# ProjSchematic.net
KiCad netlist of a schematic drawn in EAGLE
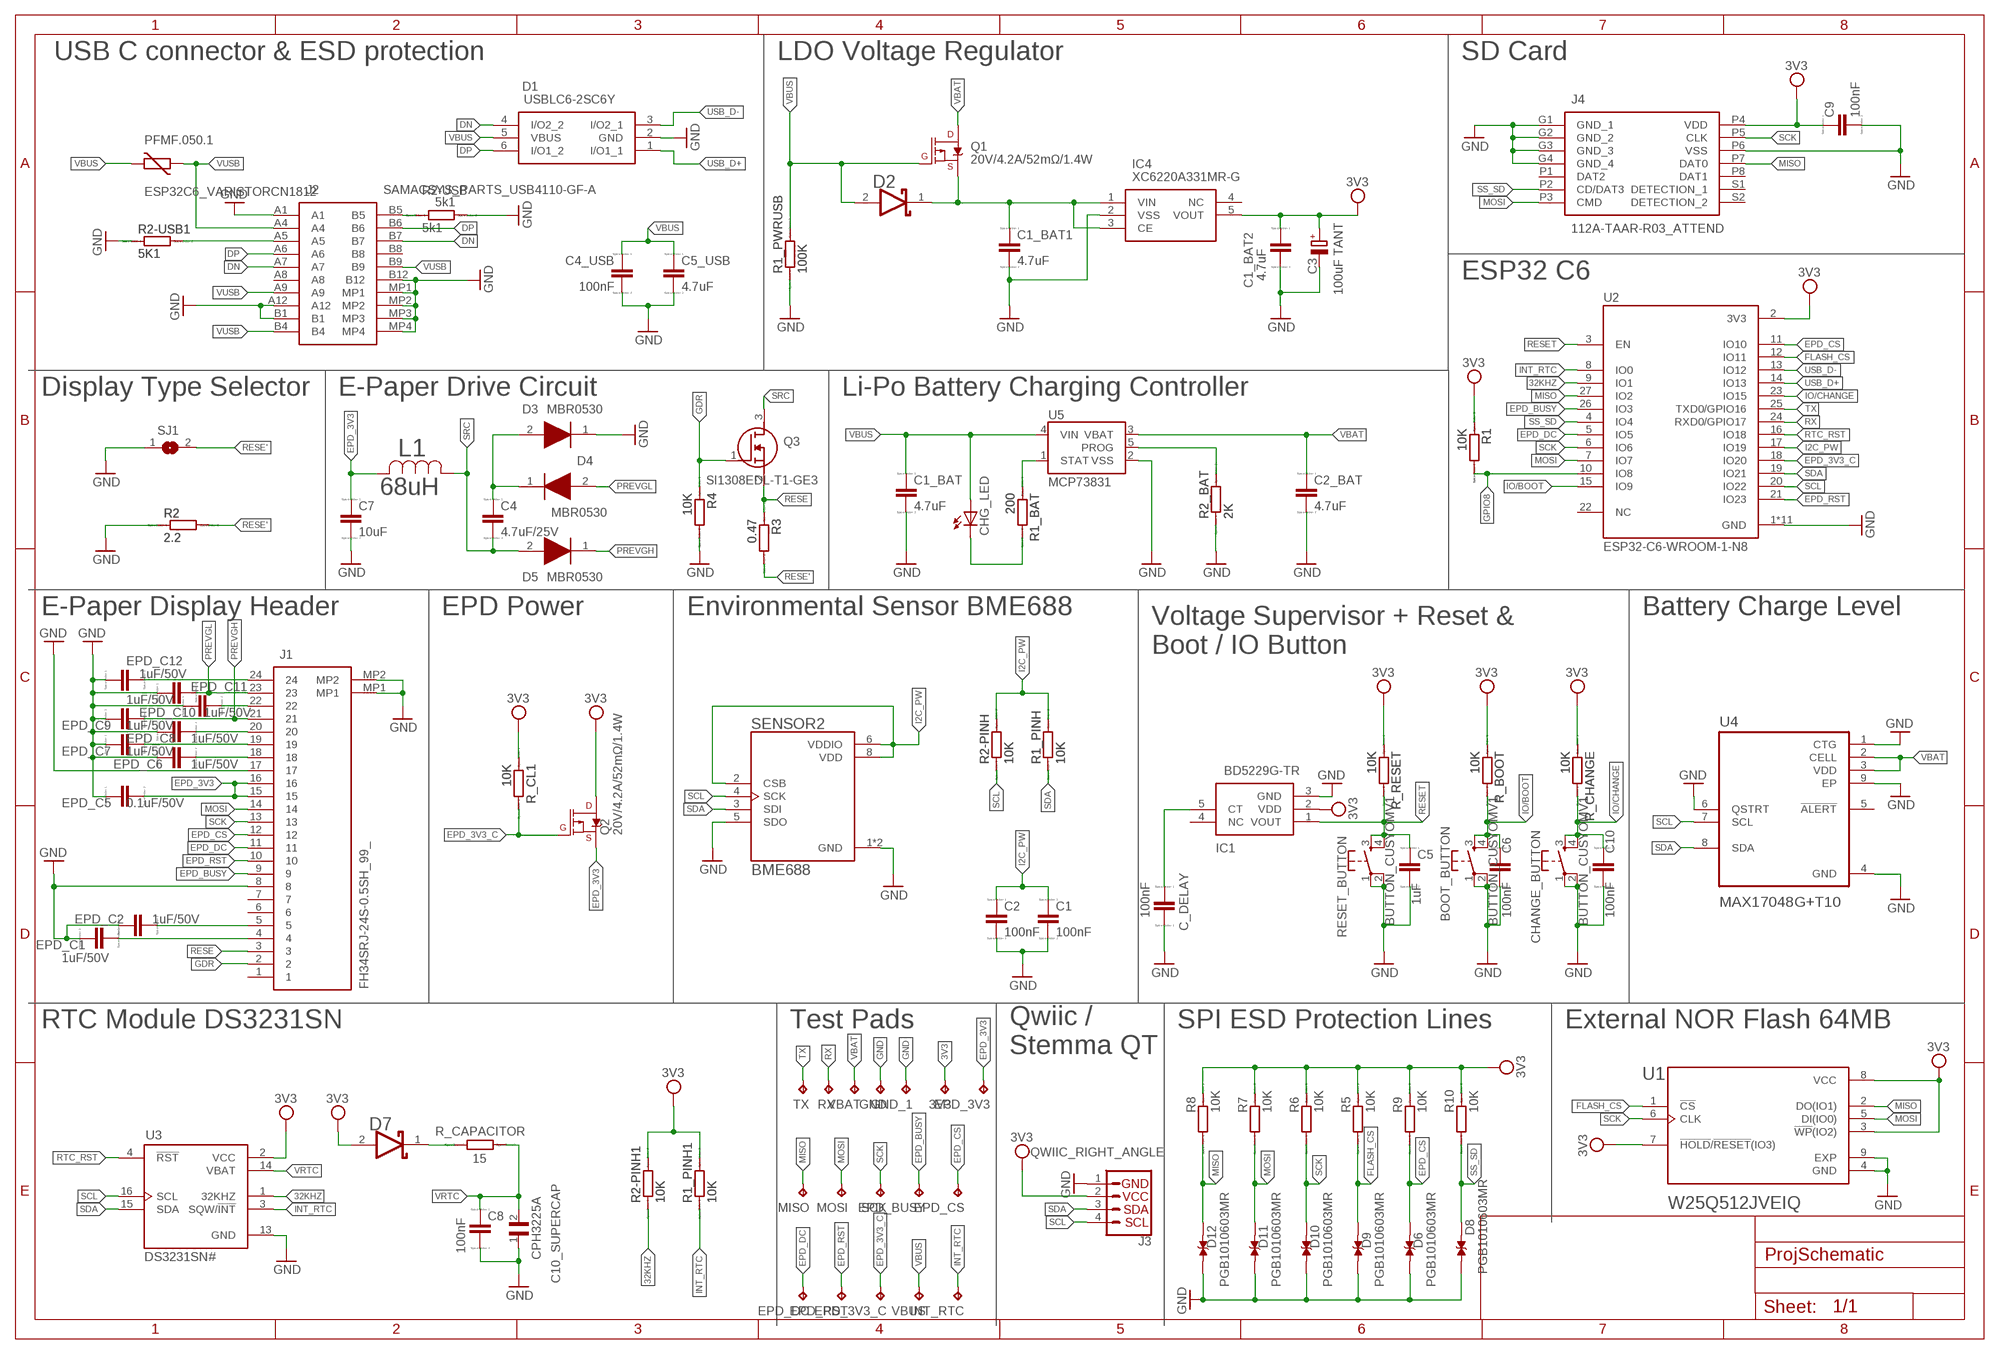
[diagram p0: schematic, sheet 1]

(export (version "E")
  (design (tool "Eeschema 10.0.6"))
  (components
    (comp (ref "3V3")
      (value "TPTP20R")
      (footprint "eagle-import:TP20R")
      (libsource (lib "eagle-import") (part "TPTP20R"))
    )
    (comp (ref "BOOT_BUTTON")
      (value "BUTTON_CUSYOMV1")
      (footprint "eagle-import:MYBUTTON")
      (libsource (lib "eagle-import") (part "BUTTON_CUSYOMV1"))
    )
    (comp (ref "C1")
      (value "100nF")
      (footprint "eagle-import:ESP32_WROVER_EAGLE-LTSPICE_C0402")
      (libsource (lib "eagle-import") (part "ESP32_WROVER_EAGLE-LTSPICE_CC0402"))
    )
    (comp (ref "C1_BAT")
      (value "4.7uF")
      (footprint "eagle-import:ESP32_WROVER_EAGLE-LTSPICE_C0402")
      (libsource (lib "eagle-import") (part "ESP32_WROVER_EAGLE-LTSPICE_CC0402"))
    )
    (comp (ref "C1_BAT1")
      (value "4.7uF")
      (footprint "eagle-import:ESP32_WROVER_EAGLE-LTSPICE_C0402")
      (libsource (lib "eagle-import") (part "ESP32_WROVER_EAGLE-LTSPICE_CC0402"))
    )
    (comp (ref "C1_BAT2")
      (value "4.7uF")
      (footprint "eagle-import:ESP32_WROVER_EAGLE-LTSPICE_C0402")
      (libsource (lib "eagle-import") (part "ESP32_WROVER_EAGLE-LTSPICE_CC0402"))
    )
    (comp (ref "C2")
      (value "100nF")
      (footprint "eagle-import:ESP32_WROVER_EAGLE-LTSPICE_C0402")
      (libsource (lib "eagle-import") (part "ESP32_WROVER_EAGLE-LTSPICE_CC0402"))
    )
    (comp (ref "C2_BAT")
      (value "4.7uF")
      (footprint "eagle-import:ESP32_WROVER_EAGLE-LTSPICE_C0402")
      (libsource (lib "eagle-import") (part "ESP32_WROVER_EAGLE-LTSPICE_CC0402"))
    )
    (comp (ref "C3")
      (value "100uF TANT")
      (footprint "eagle-import:RCL_CT3528")
      (libsource (lib "eagle-import") (part "RCL_CPOL-EUCT3528"))
    )
    (comp (ref "C4")
      (value "4.7uF/25V")
      (footprint "eagle-import:ESP32_WROVER_EAGLE-LTSPICE_C0402")
      (libsource (lib "eagle-import") (part "ESP32_WROVER_EAGLE-LTSPICE_CC0402"))
    )
    (comp (ref "C4_USB")
      (value "100nF")
      (footprint "eagle-import:ESP32_WROVER_EAGLE-LTSPICE_C0402")
      (libsource (lib "eagle-import") (part "ESP32_WROVER_EAGLE-LTSPICE_CC0402"))
    )
    (comp (ref "C5")
      (value "1uF")
      (footprint "eagle-import:ESP32_WROVER_EAGLE-LTSPICE_C0402")
      (libsource (lib "eagle-import") (part "ESP32_WROVER_EAGLE-LTSPICE_CC0402"))
    )
    (comp (ref "C5_USB")
      (value "4.7uF")
      (footprint "eagle-import:ESP32_WROVER_EAGLE-LTSPICE_C0402")
      (libsource (lib "eagle-import") (part "ESP32_WROVER_EAGLE-LTSPICE_CC0402"))
    )
    (comp (ref "C6")
      (value "100nF")
      (footprint "eagle-import:ESP32_WROVER_EAGLE-LTSPICE_C0402")
      (libsource (lib "eagle-import") (part "ESP32_WROVER_EAGLE-LTSPICE_CC0402"))
    )
    (comp (ref "C7")
      (value "10uF")
      (footprint "eagle-import:ESP32_WROVER_EAGLE-LTSPICE_C0402")
      (libsource (lib "eagle-import") (part "ESP32_WROVER_EAGLE-LTSPICE_CC0402"))
    )
    (comp (ref "C8")
      (value "100nF")
      (footprint "eagle-import:ESP32_WROVER_EAGLE-LTSPICE_C0402")
      (libsource (lib "eagle-import") (part "ESP32_WROVER_EAGLE-LTSPICE_CC0402"))
    )
    (comp (ref "C9")
      (value "100nF")
      (footprint "eagle-import:ESP32_WROVER_EAGLE-LTSPICE_C0402")
      (libsource (lib "eagle-import") (part "ESP32_WROVER_EAGLE-LTSPICE_CC0402"))
    )
    (comp (ref "C10")
      (value "100nF")
      (footprint "eagle-import:ESP32_WROVER_EAGLE-LTSPICE_C0402")
      (libsource (lib "eagle-import") (part "ESP32_WROVER_EAGLE-LTSPICE_CC0402"))
    )
    (comp (ref "C10_SUPERCAP")
      (value "CPH3225A")
      (footprint "eagle-import:CAPCP3225X100N")
      (fields (field (name "MF") "Seiko Instruments"))
      (libsource (lib "eagle-import") (part "CPH3225A"))
    )
    (comp (ref "CHANGE_BUTTON")
      (value "BUTTON_CUSYOMV1")
      (footprint "eagle-import:MYBUTTON")
      (libsource (lib "eagle-import") (part "BUTTON_CUSYOMV1"))
    )
    (comp (ref "CHG_LED")
      (value "ADAFRUIT_LEDCHIP-LED0603")
      (footprint "eagle-import:ADAFRUIT_CHIP-LED0603")
      (libsource (lib "eagle-import") (part "ADAFRUIT_LEDCHIP-LED0603"))
    )
    (comp (ref "C_DELAY")
      (value "100nF")
      (footprint "eagle-import:ESP32_WROVER_EAGLE-LTSPICE_C0402")
      (libsource (lib "eagle-import") (part "ESP32_WROVER_EAGLE-LTSPICE_CC0402"))
    )
    (comp (ref "D1")
      (value "USBLC6-2SC6Y")
      (footprint "eagle-import:SOT95P280X145-6N")
      (fields (field (name "MF") "STMicroelectronics"))
      (libsource (lib "eagle-import") (part "USBLC6-2SC6Y"))
    )
    (comp (ref "D2")
      (value "ESP32_WROVER_AVX---SD0805S020S1R0_AVX_SD0805S020S1R0_0_0AVX_SD0805S020S1R0_0_0")
      (footprint "eagle-import:ESP32_WROVER_AVX---SD0805S020S1R0_AVX_SD0805S020S1R0_0")
      (fields
        (field (name "DIGIKEY_PART_NUMBER") "478-7800-1-ND")
        (field (name "MF") "AVX")
        (field (name "MOUSER_PART_NUMBER") "581-SD0805S020S1R0")
      )
      (libsource (lib "eagle-import") (part "ESP32_WROVER_AVX---SD0805S020S1R0_AVX_SD0805S020S1R0_0_0AVX_SD0805S020S1R0_0_0"))
    )
    (comp (ref "D3")
      (value "MBR0530")
      (footprint "eagle-import:SOD3716X135N")
      (fields (field (name "MF") "ON Semiconductor"))
      (libsource (lib "eagle-import") (part "MBR0530"))
    )
    (comp (ref "D4")
      (value "MBR0530")
      (footprint "eagle-import:SOD3716X135N")
      (fields (field (name "MF") "ON Semiconductor"))
      (libsource (lib "eagle-import") (part "MBR0530"))
    )
    (comp (ref "D5")
      (value "MBR0530")
      (footprint "eagle-import:SOD3716X135N")
      (fields (field (name "MF") "ON Semiconductor"))
      (libsource (lib "eagle-import") (part "MBR0530"))
    )
    (comp (ref "D6")
      (value "PGB1010603MR")
      (footprint "eagle-import:DIOC1608X36N")
      (fields (field (name "MF") "Littelfuse Inc."))
      (libsource (lib "eagle-import") (part "PGB1010603MR"))
    )
    (comp (ref "D7")
      (value "ESP32_WROVER_AVX---SD0805S020S1R0_AVX_SD0805S020S1R0_0_0AVX_SD0805S020S1R0_0_0")
      (footprint "eagle-import:ESP32_WROVER_AVX---SD0805S020S1R0_AVX_SD0805S020S1R0_0")
      (fields
        (field (name "DIGIKEY_PART_NUMBER") "478-7800-1-ND")
        (field (name "MF") "AVX")
        (field (name "MOUSER_PART_NUMBER") "581-SD0805S020S1R0")
      )
      (libsource (lib "eagle-import") (part "ESP32_WROVER_AVX---SD0805S020S1R0_AVX_SD0805S020S1R0_0_0AVX_SD0805S020S1R0_0_0"))
    )
    (comp (ref "D8")
      (value "PGB1010603MR")
      (footprint "eagle-import:DIOC1608X36N")
      (fields (field (name "MF") "Littelfuse Inc."))
      (libsource (lib "eagle-import") (part "PGB1010603MR"))
    )
    (comp (ref "D9")
      (value "PGB1010603MR")
      (footprint "eagle-import:DIOC1608X36N")
      (fields (field (name "MF") "Littelfuse Inc."))
      (libsource (lib "eagle-import") (part "PGB1010603MR"))
    )
    (comp (ref "D10")
      (value "PGB1010603MR")
      (footprint "eagle-import:DIOC1608X36N")
      (fields (field (name "MF") "Littelfuse Inc."))
      (libsource (lib "eagle-import") (part "PGB1010603MR"))
    )
    (comp (ref "D11")
      (value "PGB1010603MR")
      (footprint "eagle-import:DIOC1608X36N")
      (fields (field (name "MF") "Littelfuse Inc."))
      (libsource (lib "eagle-import") (part "PGB1010603MR"))
    )
    (comp (ref "D12")
      (value "PGB1010603MR")
      (footprint "eagle-import:DIOC1608X36N")
      (fields (field (name "MF") "Littelfuse Inc."))
      (libsource (lib "eagle-import") (part "PGB1010603MR"))
    )
    (comp (ref "EPD_3V3")
      (value "TPTP20R")
      (footprint "eagle-import:TP20R")
      (libsource (lib "eagle-import") (part "TPTP20R"))
    )
    (comp (ref "EPD_3V3_C")
      (value "TPTP20R")
      (footprint "eagle-import:TP20R")
      (libsource (lib "eagle-import") (part "TPTP20R"))
    )
    (comp (ref "EPD_BUSY")
      (value "TPTP20R")
      (footprint "eagle-import:TP20R")
      (libsource (lib "eagle-import") (part "TPTP20R"))
    )
    (comp (ref "EPD_C1")
      (value "1uF/50V")
      (footprint "eagle-import:ESP32_WROVER_EAGLE-LTSPICE_C0402")
      (libsource (lib "eagle-import") (part "ESP32_WROVER_EAGLE-LTSPICE_CC0402"))
    )
    (comp (ref "EPD_C2")
      (value "1uF/50V")
      (footprint "eagle-import:ESP32_WROVER_EAGLE-LTSPICE_C0402")
      (libsource (lib "eagle-import") (part "ESP32_WROVER_EAGLE-LTSPICE_CC0402"))
    )
    (comp (ref "EPD_C5")
      (value "0.1uF/50V")
      (footprint "eagle-import:ESP32_WROVER_EAGLE-LTSPICE_C0402")
      (libsource (lib "eagle-import") (part "ESP32_WROVER_EAGLE-LTSPICE_CC0402"))
    )
    (comp (ref "EPD_C6")
      (value "1uF/50V")
      (footprint "eagle-import:ESP32_WROVER_EAGLE-LTSPICE_C0402")
      (libsource (lib "eagle-import") (part "ESP32_WROVER_EAGLE-LTSPICE_CC0402"))
    )
    (comp (ref "EPD_C7")
      (value "1uF/50V")
      (footprint "eagle-import:ESP32_WROVER_EAGLE-LTSPICE_C0402")
      (libsource (lib "eagle-import") (part "ESP32_WROVER_EAGLE-LTSPICE_CC0402"))
    )
    (comp (ref "EPD_C8")
      (value "1uF/50V")
      (footprint "eagle-import:ESP32_WROVER_EAGLE-LTSPICE_C0402")
      (libsource (lib "eagle-import") (part "ESP32_WROVER_EAGLE-LTSPICE_CC0402"))
    )
    (comp (ref "EPD_C9")
      (value "1uF/50V")
      (footprint "eagle-import:ESP32_WROVER_EAGLE-LTSPICE_C0402")
      (libsource (lib "eagle-import") (part "ESP32_WROVER_EAGLE-LTSPICE_CC0402"))
    )
    (comp (ref "EPD_C10")
      (value "1uF/50V")
      (footprint "eagle-import:ESP32_WROVER_EAGLE-LTSPICE_C0402")
      (libsource (lib "eagle-import") (part "ESP32_WROVER_EAGLE-LTSPICE_CC0402"))
    )
    (comp (ref "EPD_C11")
      (value "1uF/50V")
      (footprint "eagle-import:ESP32_WROVER_EAGLE-LTSPICE_C0402")
      (libsource (lib "eagle-import") (part "ESP32_WROVER_EAGLE-LTSPICE_CC0402"))
    )
    (comp (ref "EPD_C12")
      (value "1uF/50V")
      (footprint "eagle-import:ESP32_WROVER_EAGLE-LTSPICE_C0402")
      (libsource (lib "eagle-import") (part "ESP32_WROVER_EAGLE-LTSPICE_CC0402"))
    )
    (comp (ref "EPD_CS")
      (value "TPTP20R")
      (footprint "eagle-import:TP20R")
      (libsource (lib "eagle-import") (part "TPTP20R"))
    )
    (comp (ref "EPD_DC")
      (value "TPTP20R")
      (footprint "eagle-import:TP20R")
      (libsource (lib "eagle-import") (part "TPTP20R"))
    )
    (comp (ref "EPD_RST")
      (value "TPTP20R")
      (footprint "eagle-import:TP20R")
      (libsource (lib "eagle-import") (part "TPTP20R"))
    )
    (comp (ref "GND")
      (value "TPTP20R")
      (footprint "eagle-import:TP20R")
      (libsource (lib "eagle-import") (part "TPTP20R"))
    )
    (comp (ref "GND_1")
      (value "TPTP20R")
      (footprint "eagle-import:TP20R")
      (libsource (lib "eagle-import") (part "TPTP20R"))
    )
    (comp (ref "IC1")
      (value "BD5229G-TR")
      (footprint "eagle-import:SOT95P280X125-5N")
      (fields (field (name "MOUSER_PART_NUMBER") "755-BD5229G-TR"))
      (libsource (lib "eagle-import") (part "BD5229G-TR"))
    )
    (comp (ref "IC4")
      (value "XC6220A331MR-G")
      (footprint "eagle-import:SOT95P280X120-5N")
      (fields (field (name "MOUSER_PART_NUMBER") "865-XC6220A331MR-G"))
      (libsource (lib "eagle-import") (part "XC6220A331MR-G"))
    )
    (comp (ref "INT_RTC")
      (value "TPTP20R")
      (footprint "eagle-import:TP20R")
      (libsource (lib "eagle-import") (part "TPTP20R"))
    )
    (comp (ref "J1")
      (value "FH34SRJ-24S-0.5SH_99_")
      (footprint "eagle-import:FH34SRJ24S05SH99")
      (fields
        (field (name "MANUFACTURER_PART_NUMBER") "FH34SRJ-24S-0.5SH(99)")
        (field (name "MOUSER_PART_NUMBER") "798-FH34SRJ24S05SH99")
      )
      (libsource (lib "eagle-import") (part "FH34SRJ-24S-0.5SH_99_"))
    )
    (comp (ref "J2")
      (value "SAMACSYS_PARTS_USB4110-GF-A")
      (footprint "eagle-import:SAMACSYS_PARTS_USB4110GFA")
      (fields
        (field (name "MANUFACTURER_PART_NUMBER") "USB4110-GF-A")
        (field (name "MOUSER_PART_NUMBER") "640-USB4110-GF-A")
      )
      (libsource (lib "eagle-import") (part "SAMACSYS_PARTS_USB4110-GF-A"))
    )
    (comp (ref "J3")
      (value "QWIIC_RIGHT_ANGLE")
      (footprint "eagle-import:JST04_1MM_RA")
      (libsource (lib "eagle-import") (part "QWIIC_CONNECTORJS-1MM"))
    )
    (comp (ref "J4")
      (value "112A-TAAR-R03_ATTEND")
      (footprint "eagle-import:112ATAARR03ATTEND")
      (fields (field (name "MANUFACTURER_PART_NUMBER") "112A-TAAR-R03 ATTEND"))
      (libsource (lib "eagle-import") (part "112A-TAAR-R03_ATTEND"))
    )
    (comp (ref "L1")
      (value "68uH")
      (footprint "eagle-import:IND_4828-WE-TPC_WRE")
      (fields
        (field (name "MANUFACTURER_PART_NUMBER") "744043680")
        (field (name "COPYRIGHT") "Copyright (C) 2024 Ultra Librarian. All rights reserved.")
      )
      (libsource (lib "eagle-import") (part "744043680IND_4828-WE-TPC_WRE"))
    )
    (comp (ref "MISO")
      (value "TPTP20R")
      (footprint "eagle-import:TP20R")
      (libsource (lib "eagle-import") (part "TPTP20R"))
    )
    (comp (ref "MOSI")
      (value "TPTP20R")
      (footprint "eagle-import:TP20R")
      (libsource (lib "eagle-import") (part "TPTP20R"))
    )
    (comp (ref "PFMF.050.1")
      (value "ESP32C6_VARISTORCN1812")
      (footprint "eagle-import:ESP32C6_VARISTOR_CT_CN1812")
      (libsource (lib "eagle-import") (part "ESP32C6_VARISTORCN1812"))
    )
    (comp (ref "Q1")
      (value "20V/4.2A/52mΩ/1.4W")
      (footprint "eagle-import:ESP32_WROVER_SPARKFUN-DISCRETESEMI_SOT23-3")
      (libsource (lib "eagle-import") (part "ESP32_WROVER_SPARKFUN-DISCRETESEMI_MOSFET_PCH-DMG2305UX-7"))
    )
    (comp (ref "Q2")
      (value "20V/4.2A/52mΩ/1.4W")
      (footprint "eagle-import:ESP32_WROVER_SPARKFUN-DISCRETESEMI_SOT23-3")
      (libsource (lib "eagle-import") (part "ESP32_WROVER_SPARKFUN-DISCRETESEMI_MOSFET_PCH-DMG2305UX-7"))
    )
    (comp (ref "Q3")
      (value "SI1308EDL-T1-GE3")
      (footprint "eagle-import:SOT65P210X110-3N")
      (fields (field (name "MF") "Vishay Siliconix"))
      (libsource (lib "eagle-import") (part "SI1308EDL-T1-GE3"))
    )
    (comp (ref "R1")
      (value "10K")
      (footprint "eagle-import:ESP32_WROVER_EAGLE-LTSPICE_R0402")
      (libsource (lib "eagle-import") (part "ESP32_WROVER_EAGLE-LTSPICE_RR0402"))
    )
    (comp (ref "R1_BAT")
      (value "200")
      (footprint "eagle-import:ESP32_WROVER_EAGLE-LTSPICE_R0402")
      (libsource (lib "eagle-import") (part "ESP32_WROVER_EAGLE-LTSPICE_RR0402"))
    )
    (comp (ref "R1_PINH")
      (value "10K")
      (footprint "eagle-import:ESP32_WROVER_EAGLE-LTSPICE_R0402")
      (libsource (lib "eagle-import") (part "ESP32_WROVER_EAGLE-LTSPICE_RR0402"))
    )
    (comp (ref "R1_PINH1")
      (value "10K")
      (footprint "eagle-import:ESP32_WROVER_EAGLE-LTSPICE_R0402")
      (libsource (lib "eagle-import") (part "ESP32_WROVER_EAGLE-LTSPICE_RR0402"))
    )
    (comp (ref "R1_PWRUSB")
      (value "100K")
      (footprint "eagle-import:ESP32_WROVER_EAGLE-LTSPICE_R0402")
      (libsource (lib "eagle-import") (part "ESP32_WROVER_EAGLE-LTSPICE_RR0402"))
    )
    (comp (ref "R2")
      (value "2.2")
      (footprint "eagle-import:ESP32_WROVER_EAGLE-LTSPICE_R0402")
      (libsource (lib "eagle-import") (part "ESP32_WROVER_EAGLE-LTSPICE_RR0402"))
    )
    (comp (ref "R2-PINH")
      (value "10K")
      (footprint "eagle-import:ESP32_WROVER_EAGLE-LTSPICE_R0402")
      (libsource (lib "eagle-import") (part "ESP32_WROVER_EAGLE-LTSPICE_RR0402"))
    )
    (comp (ref "R2-PINH1")
      (value "10K")
      (footprint "eagle-import:ESP32_WROVER_EAGLE-LTSPICE_R0402")
      (libsource (lib "eagle-import") (part "ESP32_WROVER_EAGLE-LTSPICE_RR0402"))
    )
    (comp (ref "R2-USB")
      (value "5k1")
      (footprint "eagle-import:ESP32_WROVER_EAGLE-LTSPICE_R0402")
      (libsource (lib "eagle-import") (part "ESP32_WROVER_EAGLE-LTSPICE_RR0402"))
    )
    (comp (ref "R2-USB1")
      (value "5K1")
      (footprint "eagle-import:ESP32_WROVER_EAGLE-LTSPICE_R0402")
      (libsource (lib "eagle-import") (part "ESP32_WROVER_EAGLE-LTSPICE_RR0402"))
    )
    (comp (ref "R2_BAT")
      (value "2K")
      (footprint "eagle-import:ESP32_WROVER_EAGLE-LTSPICE_R0402")
      (libsource (lib "eagle-import") (part "ESP32_WROVER_EAGLE-LTSPICE_RR0402"))
    )
    (comp (ref "R3")
      (value "0.47")
      (footprint "eagle-import:ESP32_WROVER_EAGLE-LTSPICE_R0402")
      (libsource (lib "eagle-import") (part "ESP32_WROVER_EAGLE-LTSPICE_RR0402"))
    )
    (comp (ref "R4")
      (value "10K")
      (footprint "eagle-import:ESP32_WROVER_EAGLE-LTSPICE_R0402")
      (libsource (lib "eagle-import") (part "ESP32_WROVER_EAGLE-LTSPICE_RR0402"))
    )
    (comp (ref "R5")
      (value "10K")
      (footprint "eagle-import:ESP32_WROVER_EAGLE-LTSPICE_R0402")
      (libsource (lib "eagle-import") (part "ESP32_WROVER_EAGLE-LTSPICE_RR0402"))
    )
    (comp (ref "R6")
      (value "10K")
      (footprint "eagle-import:ESP32_WROVER_EAGLE-LTSPICE_R0402")
      (libsource (lib "eagle-import") (part "ESP32_WROVER_EAGLE-LTSPICE_RR0402"))
    )
    (comp (ref "R7")
      (value "10K")
      (footprint "eagle-import:ESP32_WROVER_EAGLE-LTSPICE_R0402")
      (libsource (lib "eagle-import") (part "ESP32_WROVER_EAGLE-LTSPICE_RR0402"))
    )
    (comp (ref "R8")
      (value "10K")
      (footprint "eagle-import:ESP32_WROVER_EAGLE-LTSPICE_R0402")
      (libsource (lib "eagle-import") (part "ESP32_WROVER_EAGLE-LTSPICE_RR0402"))
    )
    (comp (ref "R9")
      (value "10K")
      (footprint "eagle-import:ESP32_WROVER_EAGLE-LTSPICE_R0402")
      (libsource (lib "eagle-import") (part "ESP32_WROVER_EAGLE-LTSPICE_RR0402"))
    )
    (comp (ref "R10")
      (value "10K")
      (footprint "eagle-import:ESP32_WROVER_EAGLE-LTSPICE_R0402")
      (libsource (lib "eagle-import") (part "ESP32_WROVER_EAGLE-LTSPICE_RR0402"))
    )
    (comp (ref "RESET_BUTTON")
      (value "BUTTON_CUSYOMV1")
      (footprint "eagle-import:MYBUTTON")
      (libsource (lib "eagle-import") (part "BUTTON_CUSYOMV1"))
    )
    (comp (ref "RX")
      (value "TPTP20R")
      (footprint "eagle-import:TP20R")
      (libsource (lib "eagle-import") (part "TPTP20R"))
    )
    (comp (ref "R_BOOT")
      (value "10K")
      (footprint "eagle-import:ESP32_WROVER_EAGLE-LTSPICE_R0402")
      (libsource (lib "eagle-import") (part "ESP32_WROVER_EAGLE-LTSPICE_RR0402"))
    )
    (comp (ref "R_CAPACITOR")
      (value "15")
      (footprint "eagle-import:ESP32_WROVER_EAGLE-LTSPICE_R0402")
      (libsource (lib "eagle-import") (part "ESP32_WROVER_EAGLE-LTSPICE_RR0402"))
    )
    (comp (ref "R_CHANGE")
      (value "10K")
      (footprint "eagle-import:ESP32_WROVER_EAGLE-LTSPICE_R0402")
      (libsource (lib "eagle-import") (part "ESP32_WROVER_EAGLE-LTSPICE_RR0402"))
    )
    (comp (ref "R_CL1")
      (value "10K")
      (footprint "eagle-import:ESP32_WROVER_EAGLE-LTSPICE_R0402")
      (libsource (lib "eagle-import") (part "ESP32_WROVER_EAGLE-LTSPICE_RR0402"))
    )
    (comp (ref "R_RESET")
      (value "10K")
      (footprint "eagle-import:ESP32_WROVER_EAGLE-LTSPICE_R0402")
      (libsource (lib "eagle-import") (part "ESP32_WROVER_EAGLE-LTSPICE_RR0402"))
    )
    (comp (ref "SCK")
      (value "TPTP20R")
      (footprint "eagle-import:TP20R")
      (libsource (lib "eagle-import") (part "TPTP20R"))
    )
    (comp (ref "SENSOR2")
      (value "BME688")
      (footprint "eagle-import:ESP32_WROVER_BME680_PSON80P300X300X100-8N")
      (fields (field (name "MF") "Bosch Sensortec") (field (name "MP") "BME680"))
      (libsource (lib "eagle-import") (part "ESP32_WROVER_BME680_BME680"))
    )
    (comp (ref "SJ1") (value "SJ") (footprint "eagle-import:SJ") (libsource (lib "eagle-import") (part "SJ")))
    (comp (ref "TX")
      (value "TPTP20R")
      (footprint "eagle-import:TP20R")
      (libsource (lib "eagle-import") (part "TPTP20R"))
    )
    (comp (ref "U1")
      (value "W25Q512JVEIQ")
      (footprint "eagle-import:SON127P600X800X80-9N")
      (fields (field (name "MF") "Winbond Electronics"))
      (libsource (lib "eagle-import") (part "W25Q512JVEIQ"))
    )
    (comp (ref "U2")
      (value "ESP32-C6-WROOM-1-N8")
      (footprint "eagle-import:XCVR_ESP32-C6-WROOM-1-N8")
      (fields (field (name "MF") "Espressif Systems"))
      (libsource (lib "eagle-import") (part "ESP32-C6-WROOM-1-N8"))
    )
    (comp (ref "U3")
      (value "DS3231SN#")
      (footprint "eagle-import:SOIC127P1032X265-16N")
      (fields (field (name "MF") "Analog Devices"))
      (libsource (lib "eagle-import") (part "DS3231SN#"))
    )
    (comp (ref "U4")
      (value "MAX17048G+T10")
      (footprint "eagle-import:SON50P200X200X80-9N")
      (fields (field (name "MF") "Analog Devices"))
      (libsource (lib "eagle-import") (part "MAX17048G+T10"))
    )
    (comp (ref "U5")
      (value "MCP73831")
      (footprint "eagle-import:ESP32_WROVER_SPARKFUN-IC-POWER_SOT23-5")
      (libsource (lib "eagle-import") (part "ESP32_WROVER_SPARKFUN-IC-POWER_MCP73831"))
    )
    (comp (ref "VBAT")
      (value "TPTP20R")
      (footprint "eagle-import:TP20R")
      (libsource (lib "eagle-import") (part "TPTP20R"))
    )
    (comp (ref "VBUS")
      (value "TPTP20R")
      (footprint "eagle-import:TP20R")
      (libsource (lib "eagle-import") (part "TPTP20R"))
    )
  )
  (nets
    (net (code "1") (name "3V3") (class "Default")
      (node (ref "3V3") (pin "TP") (pinfunction "TP_TP") (pintype "input"))
      (node (ref "C1_BAT2") (pin "1") (pinfunction "1_1") (pintype "passive"))
      (node (ref "C3") (pin "+") (pinfunction "+_+") (pintype "passive"))
      (node (ref "C9") (pin "1") (pinfunction "1_1") (pintype "passive"))
      (node (ref "D7") (pin "2") (pinfunction "ANODE_2") (pintype "bidirectional"))
      (node (ref "IC1") (pin "2") (pinfunction "VDD_2") (pintype "bidirectional"))
      (node (ref "IC4") (pin "5") (pinfunction "VOUT_5") (pintype "bidirectional"))
      (node (ref "J3") (pin "2") (pinfunction "2_2") (pintype "power_in"))
      (node (ref "J4") (pin "P4") (pinfunction "VDD_P4") (pintype "bidirectional"))
      (node (ref "Q2") (pin "3") (pinfunction "D_3") (pintype "bidirectional"))
      (node (ref "R1") (pin "1") (pinfunction "1_1") (pintype "passive"))
      (node (ref "R10") (pin "2") (pinfunction "2_2") (pintype "passive"))
      (node (ref "R1_PINH1") (pin "2") (pinfunction "2_2") (pintype "passive"))
      (node (ref "R2-PINH1") (pin "2") (pinfunction "2_2") (pintype "passive"))
      (node (ref "R5") (pin "2") (pinfunction "2_2") (pintype "passive"))
      (node (ref "R6") (pin "2") (pinfunction "2_2") (pintype "passive"))
      (node (ref "R7") (pin "2") (pinfunction "2_2") (pintype "passive"))
      (node (ref "R8") (pin "2") (pinfunction "2_2") (pintype "passive"))
      (node (ref "R9") (pin "2") (pinfunction "2_2") (pintype "passive"))
      (node (ref "R_BOOT") (pin "1") (pinfunction "1_1") (pintype "passive"))
      (node (ref "R_CHANGE") (pin "1") (pinfunction "1_1") (pintype "passive"))
      (node (ref "R_CL1") (pin "1") (pinfunction "1_1") (pintype "passive"))
      (node (ref "R_RESET") (pin "1") (pinfunction "1_1") (pintype "passive"))
      (node (ref "U1") (pin "3") (pinfunction "~{WP}(IO2)_3") (pintype "bidirectional"))
      (node (ref "U1") (pin "7") (pinfunction "~{HOLD}/~{RESET}(IO3)_7") (pintype "bidirectional"))
      (node (ref "U1") (pin "8") (pinfunction "VCC_8") (pintype "power_in"))
      (node (ref "U2") (pin "2") (pinfunction "3V3_2") (pintype "power_in"))
      (node (ref "U3") (pin "2") (pinfunction "VCC_2") (pintype "power_in"))
    )
    (net (code "2") (name "32KHZ") (class "Default")
      (node (ref "R2-PINH1") (pin "1") (pinfunction "1_1") (pintype "passive"))
      (node (ref "U2") (pin "9") (pinfunction "IO1_9") (pintype "bidirectional"))
      (node (ref "U3") (pin "1") (pinfunction "32KHZ_1") (pintype "output"))
    )
    (net (code "3") (name "DN") (class "Default")
      (node (ref "D1") (pin "4") (pinfunction "I/O2_2_4") (pintype "bidirectional"))
      (node (ref "J2") (pin "A7") (pinfunction "A7_A7") (pintype "bidirectional"))
      (node (ref "J2") (pin "B7") (pinfunction "B7_B7") (pintype "bidirectional"))
    )
    (net (code "4") (name "DP") (class "Default")
      (node (ref "D1") (pin "6") (pinfunction "I/O1_2_6") (pintype "bidirectional"))
      (node (ref "J2") (pin "A6") (pinfunction "A6_A6") (pintype "bidirectional"))
      (node (ref "J2") (pin "B6") (pinfunction "B6_B6") (pintype "bidirectional"))
    )
    (net (code "5") (name "EPD_3V3") (class "Default")
      (node (ref "C7") (pin "1") (pinfunction "1_1") (pintype "passive"))
      (node (ref "EPD_3V3") (pin "TP") (pinfunction "TP_TP") (pintype "input"))
      (node (ref "EPD_C5") (pin "2") (pinfunction "2_2") (pintype "passive"))
      (node (ref "J1") (pin "15") (pinfunction "15_15") (pintype "bidirectional"))
      (node (ref "J1") (pin "16") (pinfunction "16_16") (pintype "bidirectional"))
      (node (ref "L1") (pin "2") (pinfunction "2_2") (pintype "passive"))
      (node (ref "Q2") (pin "2") (pinfunction "S_2") (pintype "bidirectional"))
    )
    (net (code "6") (name "EPD_3V3_C") (class "Default")
      (node (ref "EPD_3V3_C") (pin "TP") (pinfunction "TP_TP") (pintype "input"))
      (node (ref "Q2") (pin "1") (pinfunction "G_1") (pintype "bidirectional"))
      (node (ref "R_CL1") (pin "2") (pinfunction "2_2") (pintype "passive"))
      (node (ref "U2") (pin "18") (pinfunction "IO20_18") (pintype "bidirectional"))
    )
    (net (code "7") (name "EPD_BUSY") (class "Default")
      (node (ref "EPD_BUSY") (pin "TP") (pinfunction "TP_TP") (pintype "input"))
      (node (ref "J1") (pin "9") (pinfunction "9_9") (pintype "bidirectional"))
      (node (ref "U2") (pin "26") (pinfunction "IO3_26") (pintype "bidirectional"))
    )
    (net (code "8") (name "EPD_CS") (class "Default")
      (node (ref "D6") (pin "2") (pinfunction "2_2") (pintype "passive"))
      (node (ref "EPD_CS") (pin "TP") (pinfunction "TP_TP") (pintype "input"))
      (node (ref "J1") (pin "12") (pinfunction "12_12") (pintype "bidirectional"))
      (node (ref "R9") (pin "1") (pinfunction "1_1") (pintype "passive"))
      (node (ref "U2") (pin "11") (pinfunction "IO10_11") (pintype "bidirectional"))
    )
    (net (code "9") (name "EPD_DC") (class "Default")
      (node (ref "EPD_DC") (pin "TP") (pinfunction "TP_TP") (pintype "input"))
      (node (ref "J1") (pin "11") (pinfunction "11_11") (pintype "bidirectional"))
      (node (ref "U2") (pin "5") (pinfunction "IO5_5") (pintype "bidirectional"))
    )
    (net (code "10") (name "EPD_RST") (class "Default")
      (node (ref "EPD_RST") (pin "TP") (pinfunction "TP_TP") (pintype "input"))
      (node (ref "J1") (pin "10") (pinfunction "10_10") (pintype "bidirectional"))
      (node (ref "U2") (pin "21") (pinfunction "IO23_21") (pintype "bidirectional"))
    )
    (net (code "11") (name "FLASH_CS") (class "Default")
      (node (ref "D9") (pin "2") (pinfunction "2_2") (pintype "passive"))
      (node (ref "R5") (pin "1") (pinfunction "1_1") (pintype "passive"))
      (node (ref "U1") (pin "1") (pinfunction "~{CS}_1") (pintype "input"))
      (node (ref "U2") (pin "12") (pinfunction "IO11_12") (pintype "bidirectional"))
    )
    (net (code "12") (name "GDR") (class "Default")
      (node (ref "J1") (pin "2") (pinfunction "2_2") (pintype "bidirectional"))
      (node (ref "Q3") (pin "1") (pinfunction "G_1") (pintype "bidirectional"))
      (node (ref "R4") (pin "1") (pinfunction "1_1") (pintype "passive"))
    )
    (net (code "13") (name "GND") (class "Default")
      (node (ref "BOOT_BUTTON") (pin "1") (pinfunction "1_1") (pintype "passive"))
      (node (ref "BOOT_BUTTON") (pin "2") (pinfunction "2_2") (pintype "passive"))
      (node (ref "C1") (pin "2") (pinfunction "2_2") (pintype "passive"))
      (node (ref "C10") (pin "2") (pinfunction "2_2") (pintype "passive"))
      (node (ref "C10_SUPERCAP") (pin "1") (pinfunction "1_1") (pintype "passive"))
      (node (ref "C1_BAT") (pin "2") (pinfunction "2_2") (pintype "passive"))
      (node (ref "C1_BAT1") (pin "2") (pinfunction "2_2") (pintype "passive"))
      (node (ref "C1_BAT2") (pin "2") (pinfunction "2_2") (pintype "passive"))
      (node (ref "C2") (pin "2") (pinfunction "2_2") (pintype "passive"))
      (node (ref "C2_BAT") (pin "2") (pinfunction "2_2") (pintype "passive"))
      (node (ref "C3") (pin "-") (pinfunction "-_-") (pintype "passive"))
      (node (ref "C4_USB") (pin "2") (pinfunction "2_2") (pintype "passive"))
      (node (ref "C5") (pin "2") (pinfunction "2_2") (pintype "passive"))
      (node (ref "C5_USB") (pin "2") (pinfunction "2_2") (pintype "passive"))
      (node (ref "C6") (pin "2") (pinfunction "2_2") (pintype "passive"))
      (node (ref "C7") (pin "2") (pinfunction "2_2") (pintype "passive"))
      (node (ref "C8") (pin "2") (pinfunction "2_2") (pintype "passive"))
      (node (ref "C9") (pin "2") (pinfunction "2_2") (pintype "passive"))
      (node (ref "CHANGE_BUTTON") (pin "1") (pinfunction "1_1") (pintype "passive"))
      (node (ref "CHANGE_BUTTON") (pin "2") (pinfunction "2_2") (pintype "passive"))
      (node (ref "C_DELAY") (pin "2") (pinfunction "2_2") (pintype "passive"))
      (node (ref "D1") (pin "2") (pinfunction "GND_2") (pintype "bidirectional"))
      (node (ref "D10") (pin "1") (pinfunction "1_1") (pintype "passive"))
      (node (ref "D11") (pin "1") (pinfunction "1_1") (pintype "passive"))
      (node (ref "D12") (pin "1") (pinfunction "1_1") (pintype "passive"))
      (node (ref "D3") (pin "1") (pinfunction "K_1") (pintype "bidirectional"))
      (node (ref "D6") (pin "1") (pinfunction "1_1") (pintype "passive"))
      (node (ref "D8") (pin "1") (pinfunction "1_1") (pintype "passive"))
      (node (ref "D9") (pin "1") (pinfunction "1_1") (pintype "passive"))
      (node (ref "EPD_C1") (pin "2") (pinfunction "2_2") (pintype "passive"))
      (node (ref "EPD_C10") (pin "1") (pinfunction "1_1") (pintype "passive"))
      (node (ref "EPD_C11") (pin "1") (pinfunction "1_1") (pintype "passive"))
      (node (ref "EPD_C12") (pin "1") (pinfunction "1_1") (pintype "passive"))
      (node (ref "EPD_C2") (pin "2") (pinfunction "2_2") (pintype "passive"))
      (node (ref "EPD_C5") (pin "1") (pinfunction "1_1") (pintype "passive"))
      (node (ref "EPD_C6") (pin "1") (pinfunction "1_1") (pintype "passive"))
      (node (ref "EPD_C7") (pin "1") (pinfunction "1_1") (pintype "passive"))
      (node (ref "EPD_C8") (pin "1") (pinfunction "1_1") (pintype "passive"))
      (node (ref "EPD_C9") (pin "1") (pinfunction "1_1") (pintype "passive"))
      (node (ref "GND") (pin "TP") (pinfunction "TP_TP") (pintype "input"))
      (node (ref "GND_1") (pin "TP") (pinfunction "TP_TP") (pintype "input"))
      (node (ref "IC1") (pin "3") (pinfunction "GND_3") (pintype "bidirectional"))
      (node (ref "IC4") (pin "2") (pinfunction "VSS_2") (pintype "bidirectional"))
      (node (ref "J1") (pin "17") (pinfunction "17_17") (pintype "bidirectional"))
      (node (ref "J1") (pin "8") (pinfunction "8_8") (pintype "bidirectional"))
      (node (ref "J1") (pin "MP1") (pinfunction "MP1_MP1") (pintype "bidirectional"))
      (node (ref "J1") (pin "MP2") (pinfunction "MP2_MP2") (pintype "bidirectional"))
      (node (ref "J2") (pin "A1") (pinfunction "A1_A1") (pintype "bidirectional"))
      (node (ref "J2") (pin "A12") (pinfunction "A12_A12") (pintype "bidirectional"))
      (node (ref "J2") (pin "B1") (pinfunction "B1_B1") (pintype "bidirectional"))
      (node (ref "J2") (pin "B12") (pinfunction "B12_B12") (pintype "bidirectional"))
      (node (ref "J2") (pin "MP1") (pinfunction "MP1_MP1") (pintype "bidirectional"))
      (node (ref "J2") (pin "MP2") (pinfunction "MP2_MP2") (pintype "bidirectional"))
      (node (ref "J2") (pin "MP3") (pinfunction "MP3_MP3") (pintype "bidirectional"))
      (node (ref "J2") (pin "MP4") (pinfunction "MP4_MP4") (pintype "bidirectional"))
      (node (ref "J3") (pin "1") (pinfunction "1_1") (pintype "power_in"))
      (node (ref "J4") (pin "G1") (pinfunction "GND_1_G1") (pintype "bidirectional"))
      (node (ref "J4") (pin "G2") (pinfunction "GND_2_G2") (pintype "bidirectional"))
      (node (ref "J4") (pin "G3") (pinfunction "GND_3_G3") (pintype "bidirectional"))
      (node (ref "J4") (pin "G4") (pinfunction "GND_4_G4") (pintype "bidirectional"))
      (node (ref "J4") (pin "P6") (pinfunction "VSS_P6") (pintype "bidirectional"))
      (node (ref "R1_PWRUSB") (pin "1") (pinfunction "1_1") (pintype "passive"))
      (node (ref "R2") (pin "1") (pinfunction "1_1") (pintype "passive"))
      (node (ref "R2-USB") (pin "2") (pinfunction "2_2") (pintype "passive"))
      (node (ref "R2-USB1") (pin "1") (pinfunction "1_1") (pintype "passive"))
      (node (ref "R2_BAT") (pin "1") (pinfunction "1_1") (pintype "passive"))
      (node (ref "R4") (pin "2") (pinfunction "2_2") (pintype "passive"))
      (node (ref "RESET_BUTTON") (pin "1") (pinfunction "1_1") (pintype "passive"))
      (node (ref "RESET_BUTTON") (pin "2") (pinfunction "2_2") (pintype "passive"))
      (node (ref "SENSOR2") (pin "1") (pinfunction "GND_1") (pintype "power_in"))
      (node (ref "SENSOR2") (pin "5") (pinfunction "SDO_5") (pintype "bidirectional"))
      (node (ref "SENSOR2") (pin "7") (pinfunction "GND_7") (pintype "power_in"))
      (node (ref "SJ1") (pin "1") (pinfunction "1_1") (pintype "passive"))
      (node (ref "U1") (pin "4") (pinfunction "GND_4") (pintype "power_in"))
      (node (ref "U1") (pin "9") (pinfunction "EXP_9") (pintype "passive"))
      (node (ref "U2") (pin "1") (pinfunction "GND_1") (pintype "power_in"))
      (node (ref "U2") (pin "28") (pinfunction "GND_28") (pintype "power_in"))
      (node (ref "U2") (pin "29_1") (pinfunction "GND_29_1") (pintype "power_in"))
      (node (ref "U2") (pin "29_2") (pinfunction "GND_29_2") (pintype "power_in"))
      (node (ref "U2") (pin "29_3") (pinfunction "GND_29_3") (pintype "power_in"))
      (node (ref "U2") (pin "29_4") (pinfunction "GND_29_4") (pintype "power_in"))
      (node (ref "U2") (pin "29_5") (pinfunction "GND_29_5") (pintype "power_in"))
      (node (ref "U2") (pin "29_6") (pinfunction "GND_29_6") (pintype "power_in"))
      (node (ref "U2") (pin "29_7") (pinfunction "GND_29_7") (pintype "power_in"))
      (node (ref "U2") (pin "29_8") (pinfunction "GND_29_8") (pintype "power_in"))
      (node (ref "U2") (pin "29_9") (pinfunction "GND_29_9") (pintype "power_in"))
      (node (ref "U3") (pin "13") (pinfunction "GND_13") (pintype "power_in"))
      (node (ref "U4") (pin "1") (pinfunction "CTG_1") (pintype "power_in"))
      (node (ref "U4") (pin "4") (pinfunction "GND_4") (pintype "power_in"))
      (node (ref "U4") (pin "6") (pinfunction "QSTRT_6") (pintype "input"))
      (node (ref "U4") (pin "9") (pinfunction "EP_9") (pintype "power_in"))
      (node (ref "U5") (pin "2") (pinfunction "VSS_2") (pintype "power_in"))
    )
    (net (code "14") (name "GPIO8") (class "Default")
      (node (ref "R1") (pin "2") (pinfunction "2_2") (pintype "passive"))
      (node (ref "U2") (pin "10") (pinfunction "IO8_10") (pintype "bidirectional"))
    )
    (net (code "15") (name "I2C_PW") (class "Default")
      (node (ref "C1") (pin "1") (pinfunction "1_1") (pintype "passive"))
      (node (ref "C2") (pin "1") (pinfunction "1_1") (pintype "passive"))
      (node (ref "R1_PINH") (pin "2") (pinfunction "2_2") (pintype "passive"))
      (node (ref "R2-PINH") (pin "2") (pinfunction "2_2") (pintype "passive"))
      (node (ref "SENSOR2") (pin "2") (pinfunction "CSB_2") (pintype "input"))
      (node (ref "SENSOR2") (pin "6") (pinfunction "VDDIO_6") (pintype "power_in"))
      (node (ref "SENSOR2") (pin "8") (pinfunction "VDD_8") (pintype "power_in"))
      (node (ref "U2") (pin "17") (pinfunction "IO19_17") (pintype "bidirectional"))
    )
    (net (code "16") (name "INT_RTC") (class "Default")
      (node (ref "INT_RTC") (pin "TP") (pinfunction "TP_TP") (pintype "input"))
      (node (ref "R1_PINH1") (pin "1") (pinfunction "1_1") (pintype "passive"))
      (node (ref "U2") (pin "8") (pinfunction "IO0_8") (pintype "bidirectional"))
      (node (ref "U3") (pin "3") (pinfunction "SQW/~{INT}_3") (pintype "output"))
    )
    (net (code "17") (name "IO{slash}BOOT") (class "Default")
      (node (ref "BOOT_BUTTON") (pin "3") (pinfunction "3_3") (pintype "passive"))
      (node (ref "BOOT_BUTTON") (pin "4") (pinfunction "4_4") (pintype "passive"))
      (node (ref "C6") (pin "1") (pinfunction "1_1") (pintype "passive"))
      (node (ref "R_BOOT") (pin "2") (pinfunction "2_2") (pintype "passive"))
      (node (ref "U2") (pin "15") (pinfunction "IO9_15") (pintype "bidirectional"))
    )
    (net (code "18") (name "IO{slash}CHANGE") (class "Default")
      (node (ref "C10") (pin "1") (pinfunction "1_1") (pintype "passive"))
      (node (ref "CHANGE_BUTTON") (pin "3") (pinfunction "3_3") (pintype "passive"))
      (node (ref "CHANGE_BUTTON") (pin "4") (pinfunction "4_4") (pintype "passive"))
      (node (ref "R_CHANGE") (pin "2") (pinfunction "2_2") (pintype "passive"))
      (node (ref "U2") (pin "23") (pinfunction "IO15_23") (pintype "bidirectional"))
    )
    (net (code "19") (name "MISO") (class "Default")
      (node (ref "D12") (pin "2") (pinfunction "2_2") (pintype "passive"))
      (node (ref "J4") (pin "P7") (pinfunction "DAT0_P7") (pintype "bidirectional"))
      (node (ref "MISO") (pin "TP") (pinfunction "TP_TP") (pintype "input"))
      (node (ref "R8") (pin "1") (pinfunction "1_1") (pintype "passive"))
      (node (ref "U1") (pin "2") (pinfunction "DO(IO1)_2") (pintype "bidirectional"))
      (node (ref "U2") (pin "27") (pinfunction "IO2_27") (pintype "bidirectional"))
    )
    (net (code "20") (name "MOSI") (class "Default")
      (node (ref "D11") (pin "2") (pinfunction "2_2") (pintype "passive"))
      (node (ref "J1") (pin "14") (pinfunction "14_14") (pintype "bidirectional"))
      (node (ref "J4") (pin "P3") (pinfunction "CMD_P3") (pintype "bidirectional"))
      (node (ref "MOSI") (pin "TP") (pinfunction "TP_TP") (pintype "input"))
      (node (ref "R7") (pin "1") (pinfunction "1_1") (pintype "passive"))
      (node (ref "U1") (pin "5") (pinfunction "DI(IO0)_5") (pintype "bidirectional"))
      (node (ref "U2") (pin "7") (pinfunction "IO7_7") (pintype "bidirectional"))
    )
    (net (code "21") (name "Net-(CHG_LED-PadC)") (class "Default")
      (node (ref "CHG_LED") (pin "C") (pinfunction "C_C") (pintype "passive"))
      (node (ref "R1_BAT") (pin "2") (pinfunction "2_2") (pintype "passive"))
    )
    (net (code "22") (name "Net-(D2-CATHODE)") (class "Default")
      (node (ref "C1_BAT1") (pin "1") (pinfunction "1_1") (pintype "passive"))
      (node (ref "D2") (pin "1") (pinfunction "CATHODE_1") (pintype "bidirectional"))
      (node (ref "IC4") (pin "1") (pinfunction "VIN_1") (pintype "bidirectional"))
      (node (ref "IC4") (pin "3") (pinfunction "CE_3") (pintype "bidirectional"))
      (node (ref "Q1") (pin "2") (pinfunction "S_2") (pintype "bidirectional"))
    )
    (net (code "23") (name "Net-(D3-A)") (class "Default")
      (node (ref "C4") (pin "1") (pinfunction "1_1") (pintype "passive"))
      (node (ref "D3") (pin "2") (pinfunction "A_2") (pintype "bidirectional"))
      (node (ref "D4") (pin "1") (pinfunction "K_1") (pintype "bidirectional"))
    )
    (net (code "24") (name "Net-(D7-CATHODE)") (class "Default")
      (node (ref "D7") (pin "1") (pinfunction "CATHODE_1") (pintype "bidirectional"))
      (node (ref "R_CAPACITOR") (pin "2") (pinfunction "2_2") (pintype "passive"))
    )
    (net (code "25") (name "Net-(EPD_C1-Pad1)") (class "Default")
      (node (ref "EPD_C1") (pin "1") (pinfunction "1_1") (pintype "passive"))
      (node (ref "J1") (pin "4") (pinfunction "4_4") (pintype "bidirectional"))
    )
    (net (code "26") (name "Net-(EPD_C2-Pad1)") (class "Default")
      (node (ref "EPD_C2") (pin "1") (pinfunction "1_1") (pintype "passive"))
      (node (ref "J1") (pin "5") (pinfunction "5_5") (pintype "bidirectional"))
    )
    (net (code "27") (name "Net-(EPD_C6-Pad2)") (class "Default")
      (node (ref "EPD_C6") (pin "2") (pinfunction "2_2") (pintype "passive"))
      (node (ref "J1") (pin "18") (pinfunction "18_18") (pintype "bidirectional"))
    )
    (net (code "28") (name "Net-(EPD_C7-Pad2)") (class "Default")
      (node (ref "EPD_C7") (pin "2") (pinfunction "2_2") (pintype "passive"))
      (node (ref "J1") (pin "19") (pinfunction "19_19") (pintype "bidirectional"))
    )
    (net (code "29") (name "Net-(EPD_C8-Pad2)") (class "Default")
      (node (ref "EPD_C8") (pin "2") (pinfunction "2_2") (pintype "passive"))
      (node (ref "J1") (pin "20") (pinfunction "20_20") (pintype "bidirectional"))
    )
    (net (code "30") (name "Net-(EPD_C10-Pad2)") (class "Default")
      (node (ref "EPD_C10") (pin "2") (pinfunction "2_2") (pintype "passive"))
      (node (ref "J1") (pin "22") (pinfunction "22_22") (pintype "bidirectional"))
    )
    (net (code "31") (name "Net-(EPD_C12-Pad2)") (class "Default")
      (node (ref "EPD_C12") (pin "2") (pinfunction "2_2") (pintype "passive"))
      (node (ref "J1") (pin "24") (pinfunction "24_24") (pintype "bidirectional"))
    )
    (net (code "32") (name "Net-(IC1-CT)") (class "Default")
      (node (ref "C_DELAY") (pin "1") (pinfunction "1_1") (pintype "passive"))
      (node (ref "IC1") (pin "5") (pinfunction "CT_5") (pintype "bidirectional"))
    )
    (net (code "33") (name "Net-(J2-PadA5)") (class "Default")
      (node (ref "J2") (pin "A5") (pinfunction "A5_A5") (pintype "bidirectional"))
      (node (ref "R2-USB1") (pin "2") (pinfunction "2_2") (pintype "passive"))
    )
    (net (code "34") (name "Net-(J2-PadB5)") (class "Default")
      (node (ref "J2") (pin "B5") (pinfunction "B5_B5") (pintype "bidirectional"))
      (node (ref "R2-USB") (pin "1") (pinfunction "1_1") (pintype "passive"))
    )
    (net (code "35") (name "Net-(U5-PROG)") (class "Default")
      (node (ref "R2_BAT") (pin "2") (pinfunction "2_2") (pintype "passive"))
      (node (ref "U5") (pin "5") (pinfunction "PROG_5") (pintype "input"))
    )
    (net (code "36") (name "Net-(U5-STAT)") (class "Default")
      (node (ref "R1_BAT") (pin "1") (pinfunction "1_1") (pintype "passive"))
      (node (ref "U5") (pin "1") (pinfunction "STAT_1") (pintype "output"))
    )
    (net (code "37") (name "PREVGH") (class "Default")
      (node (ref "D5") (pin "1") (pinfunction "K_1") (pintype "bidirectional"))
      (node (ref "EPD_C9") (pin "2") (pinfunction "2_2") (pintype "passive"))
      (node (ref "J1") (pin "21") (pinfunction "21_21") (pintype "bidirectional"))
    )
    (net (code "38") (name "PREVGL") (class "Default")
      (node (ref "D4") (pin "2") (pinfunction "A_2") (pintype "bidirectional"))
      (node (ref "EPD_C11") (pin "2") (pinfunction "2_2") (pintype "passive"))
      (node (ref "J1") (pin "23") (pinfunction "23_23") (pintype "bidirectional"))
    )
    (net (code "39") (name "RESE") (class "Default")
      (node (ref "J1") (pin "3") (pinfunction "3_3") (pintype "bidirectional"))
      (node (ref "Q3") (pin "2") (pinfunction "S_2") (pintype "bidirectional"))
      (node (ref "R3") (pin "1") (pinfunction "1_1") (pintype "passive"))
    )
    (net (code "40") (name "RESE'") (class "Default")
      (node (ref "R2") (pin "2") (pinfunction "2_2") (pintype "passive"))
      (node (ref "R3") (pin "2") (pinfunction "2_2") (pintype "passive"))
      (node (ref "SJ1") (pin "2") (pinfunction "2_2") (pintype "passive"))
    )
    (net (code "41") (name "RESET") (class "Default")
      (node (ref "C5") (pin "1") (pinfunction "1_1") (pintype "passive"))
      (node (ref "IC1") (pin "1") (pinfunction "VOUT_1") (pintype "bidirectional"))
      (node (ref "RESET_BUTTON") (pin "3") (pinfunction "3_3") (pintype "passive"))
      (node (ref "RESET_BUTTON") (pin "4") (pinfunction "4_4") (pintype "passive"))
      (node (ref "R_RESET") (pin "2") (pinfunction "2_2") (pintype "passive"))
      (node (ref "U2") (pin "3") (pinfunction "EN_3") (pintype "input"))
    )
    (net (code "42") (name "RTC_RST") (class "Default")
      (node (ref "U2") (pin "16") (pinfunction "IO18_16") (pintype "bidirectional"))
      (node (ref "U3") (pin "4") (pinfunction "~{RST}_4") (pintype "input"))
    )
    (net (code "43") (name "RX") (class "Default")
      (node (ref "RX") (pin "TP") (pinfunction "TP_TP") (pintype "input"))
      (node (ref "U2") (pin "24") (pinfunction "RXD0/GPIO17_24") (pintype "bidirectional"))
    )
    (net (code "44") (name "SCK") (class "Default")
      (node (ref "D10") (pin "2") (pinfunction "2_2") (pintype "passive"))
      (node (ref "J1") (pin "13") (pinfunction "13_13") (pintype "bidirectional"))
      (node (ref "J4") (pin "P5") (pinfunction "CLK_P5") (pintype "bidirectional"))
      (node (ref "R6") (pin "1") (pinfunction "1_1") (pintype "passive"))
      (node (ref "SCK") (pin "TP") (pinfunction "TP_TP") (pintype "input"))
      (node (ref "U1") (pin "6") (pinfunction "CLK_6") (pintype "input"))
      (node (ref "U2") (pin "6") (pinfunction "IO6_6") (pintype "bidirectional"))
    )
    (net (code "45") (name "SCL") (class "Default")
      (node (ref "J3") (pin "4") (pinfunction "4_4") (pintype "passive"))
      (node (ref "R2-PINH") (pin "1") (pinfunction "1_1") (pintype "passive"))
      (node (ref "SENSOR2") (pin "4") (pinfunction "SCK_4") (pintype "input"))
      (node (ref "U2") (pin "20") (pinfunction "IO22_20") (pintype "bidirectional"))
      (node (ref "U3") (pin "16") (pinfunction "SCL_16") (pintype "input"))
      (node (ref "U4") (pin "7") (pinfunction "SCL_7") (pintype "input"))
    )
    (net (code "46") (name "SDA") (class "Default")
      (node (ref "J3") (pin "3") (pinfunction "3_3") (pintype "passive"))
      (node (ref "R1_PINH") (pin "1") (pinfunction "1_1") (pintype "passive"))
      (node (ref "SENSOR2") (pin "3") (pinfunction "SDI_3") (pintype "bidirectional"))
      (node (ref "U2") (pin "19") (pinfunction "IO21_19") (pintype "bidirectional"))
      (node (ref "U3") (pin "15") (pinfunction "SDA_15") (pintype "bidirectional"))
      (node (ref "U4") (pin "8") (pinfunction "SDA_8") (pintype "bidirectional"))
    )
    (net (code "47") (name "SRC") (class "Default")
      (node (ref "C4") (pin "2") (pinfunction "2_2") (pintype "passive"))
      (node (ref "D5") (pin "2") (pinfunction "A_2") (pintype "bidirectional"))
      (node (ref "L1") (pin "1") (pinfunction "1_1") (pintype "passive"))
      (node (ref "Q3") (pin "3") (pinfunction "D_3") (pintype "bidirectional"))
    )
    (net (code "48") (name "SS_SD") (class "Default")
      (node (ref "D8") (pin "2") (pinfunction "2_2") (pintype "passive"))
      (node (ref "J4") (pin "P2") (pinfunction "CD/DAT3_P2") (pintype "bidirectional"))
      (node (ref "R10") (pin "1") (pinfunction "1_1") (pintype "passive"))
      (node (ref "U2") (pin "4") (pinfunction "IO4_4") (pintype "bidirectional"))
    )
    (net (code "49") (name "TX") (class "Default")
      (node (ref "TX") (pin "TP") (pinfunction "TP_TP") (pintype "input"))
      (node (ref "U2") (pin "25") (pinfunction "TXD0/GPIO16_25") (pintype "bidirectional"))
    )
    (net (code "50") (name "USB_D+") (class "Default")
      (node (ref "D1") (pin "1") (pinfunction "I/O1_1_1") (pintype "bidirectional"))
      (node (ref "U2") (pin "14") (pinfunction "IO13_14") (pintype "bidirectional"))
    )
    (net (code "51") (name "USB_D-") (class "Default")
      (node (ref "D1") (pin "3") (pinfunction "I/O2_1_3") (pintype "bidirectional"))
      (node (ref "U2") (pin "13") (pinfunction "IO12_13") (pintype "bidirectional"))
    )
    (net (code "52") (name "VBAT") (class "Default")
      (node (ref "C2_BAT") (pin "1") (pinfunction "1_1") (pintype "passive"))
      (node (ref "Q1") (pin "3") (pinfunction "D_3") (pintype "bidirectional"))
      (node (ref "U4") (pin "2") (pinfunction "CELL_2") (pintype "power_in"))
      (node (ref "U4") (pin "3") (pinfunction "VDD_3") (pintype "power_in"))
      (node (ref "U5") (pin "3") (pinfunction "VBAT_3") (pintype "power_in"))
      (node (ref "VBAT") (pin "TP") (pinfunction "TP_TP") (pintype "input"))
    )
    (net (code "53") (name "VBUS") (class "Default")
      (node (ref "C1_BAT") (pin "1") (pinfunction "1_1") (pintype "passive"))
      (node (ref "C4_USB") (pin "1") (pinfunction "1_1") (pintype "passive"))
      (node (ref "C5_USB") (pin "1") (pinfunction "1_1") (pintype "passive"))
      (node (ref "CHG_LED") (pin "A") (pinfunction "A_A") (pintype "passive"))
      (node (ref "D1") (pin "5") (pinfunction "VBUS_5") (pintype "bidirectional"))
      (node (ref "D2") (pin "2") (pinfunction "ANODE_2") (pintype "bidirectional"))
      (node (ref "PFMF.050.1") (pin "2") (pinfunction "2_2") (pintype "passive"))
      (node (ref "Q1") (pin "1") (pinfunction "G_1") (pintype "bidirectional"))
      (node (ref "R1_PWRUSB") (pin "2") (pinfunction "2_2") (pintype "passive"))
      (node (ref "U5") (pin "4") (pinfunction "VIN_4") (pintype "power_in"))
      (node (ref "VBUS") (pin "TP") (pinfunction "TP_TP") (pintype "input"))
    )
    (net (code "54") (name "VRTC") (class "Default")
      (node (ref "C10_SUPERCAP") (pin "2") (pinfunction "2_2") (pintype "passive"))
      (node (ref "C8") (pin "1") (pinfunction "1_1") (pintype "passive"))
      (node (ref "R_CAPACITOR") (pin "1") (pinfunction "1_1") (pintype "passive"))
      (node (ref "U3") (pin "14") (pinfunction "VBAT_14") (pintype "power_in"))
    )
    (net (code "55") (name "VUSB") (class "Default")
      (node (ref "J2") (pin "A4") (pinfunction "A4_A4") (pintype "bidirectional"))
      (node (ref "J2") (pin "A9") (pinfunction "A9_A9") (pintype "bidirectional"))
      (node (ref "J2") (pin "B4") (pinfunction "B4_B4") (pintype "bidirectional"))
      (node (ref "J2") (pin "B9") (pinfunction "B9_B9") (pintype "bidirectional"))
      (node (ref "PFMF.050.1") (pin "1") (pinfunction "1_1") (pintype "passive"))
    )
    (net (code "56") (name "unconnected-(IC1-NC-Pad4)") (class "Default")
      (node (ref "IC1") (pin "4") (pinfunction "NC_4") (pintype "no_connect"))
    )
    (net (code "57") (name "unconnected-(IC4-NC-Pad4)") (class "Default")
      (node (ref "IC4") (pin "4") (pinfunction "NC_4") (pintype "no_connect"))
    )
    (net (code "58") (name "unconnected-(J1-Pad1)") (class "Default")
      (node (ref "J1") (pin "1") (pinfunction "1_1") (pintype "bidirectional"))
    )
    (net (code "59") (name "unconnected-(J1-Pad6)") (class "Default")
      (node (ref "J1") (pin "6") (pinfunction "6_6") (pintype "bidirectional"))
    )
    (net (code "60") (name "unconnected-(J1-Pad7)") (class "Default")
      (node (ref "J1") (pin "7") (pinfunction "7_7") (pintype "bidirectional"))
    )
    (net (code "61") (name "unconnected-(J2-PadA8)") (class "Default")
      (node (ref "J2") (pin "A8") (pinfunction "A8_A8") (pintype "bidirectional"))
    )
    (net (code "62") (name "unconnected-(J2-PadB8)") (class "Default")
      (node (ref "J2") (pin "B8") (pinfunction "B8_B8") (pintype "bidirectional"))
    )
    (net (code "63") (name "unconnected-(J4-DAT1-PadP8)") (class "Default")
      (node (ref "J4") (pin "P8") (pinfunction "DAT1_P8") (pintype "bidirectional"))
    )
    (net (code "64") (name "unconnected-(J4-DAT2-PadP1)") (class "Default")
      (node (ref "J4") (pin "P1") (pinfunction "DAT2_P1") (pintype "bidirectional"))
    )
    (net (code "65") (name "unconnected-(J4-DETECTION_1-PadS1)") (class "Default")
      (node (ref "J4") (pin "S1") (pinfunction "DETECTION_1_S1") (pintype "bidirectional"))
    )
    (net (code "66") (name "unconnected-(J4-DETECTION_2-PadS2)") (class "Default")
      (node (ref "J4") (pin "S2") (pinfunction "DETECTION_2_S2") (pintype "bidirectional"))
    )
    (net (code "67") (name "unconnected-(U2-NC-Pad22)") (class "Default")
      (node (ref "U2") (pin "22") (pinfunction "NC_22") (pintype "no_connect"))
    )
    (net (code "68") (name "unconnected-(U4-~{ALERT}-Pad5)") (class "Default")
      (node (ref "U4") (pin "5") (pinfunction "~{ALERT}_5") (pintype "output"))
    )
  )
)
